# PROG_BATT.net
KiCad netlist of a schematic drawn in EAGLE
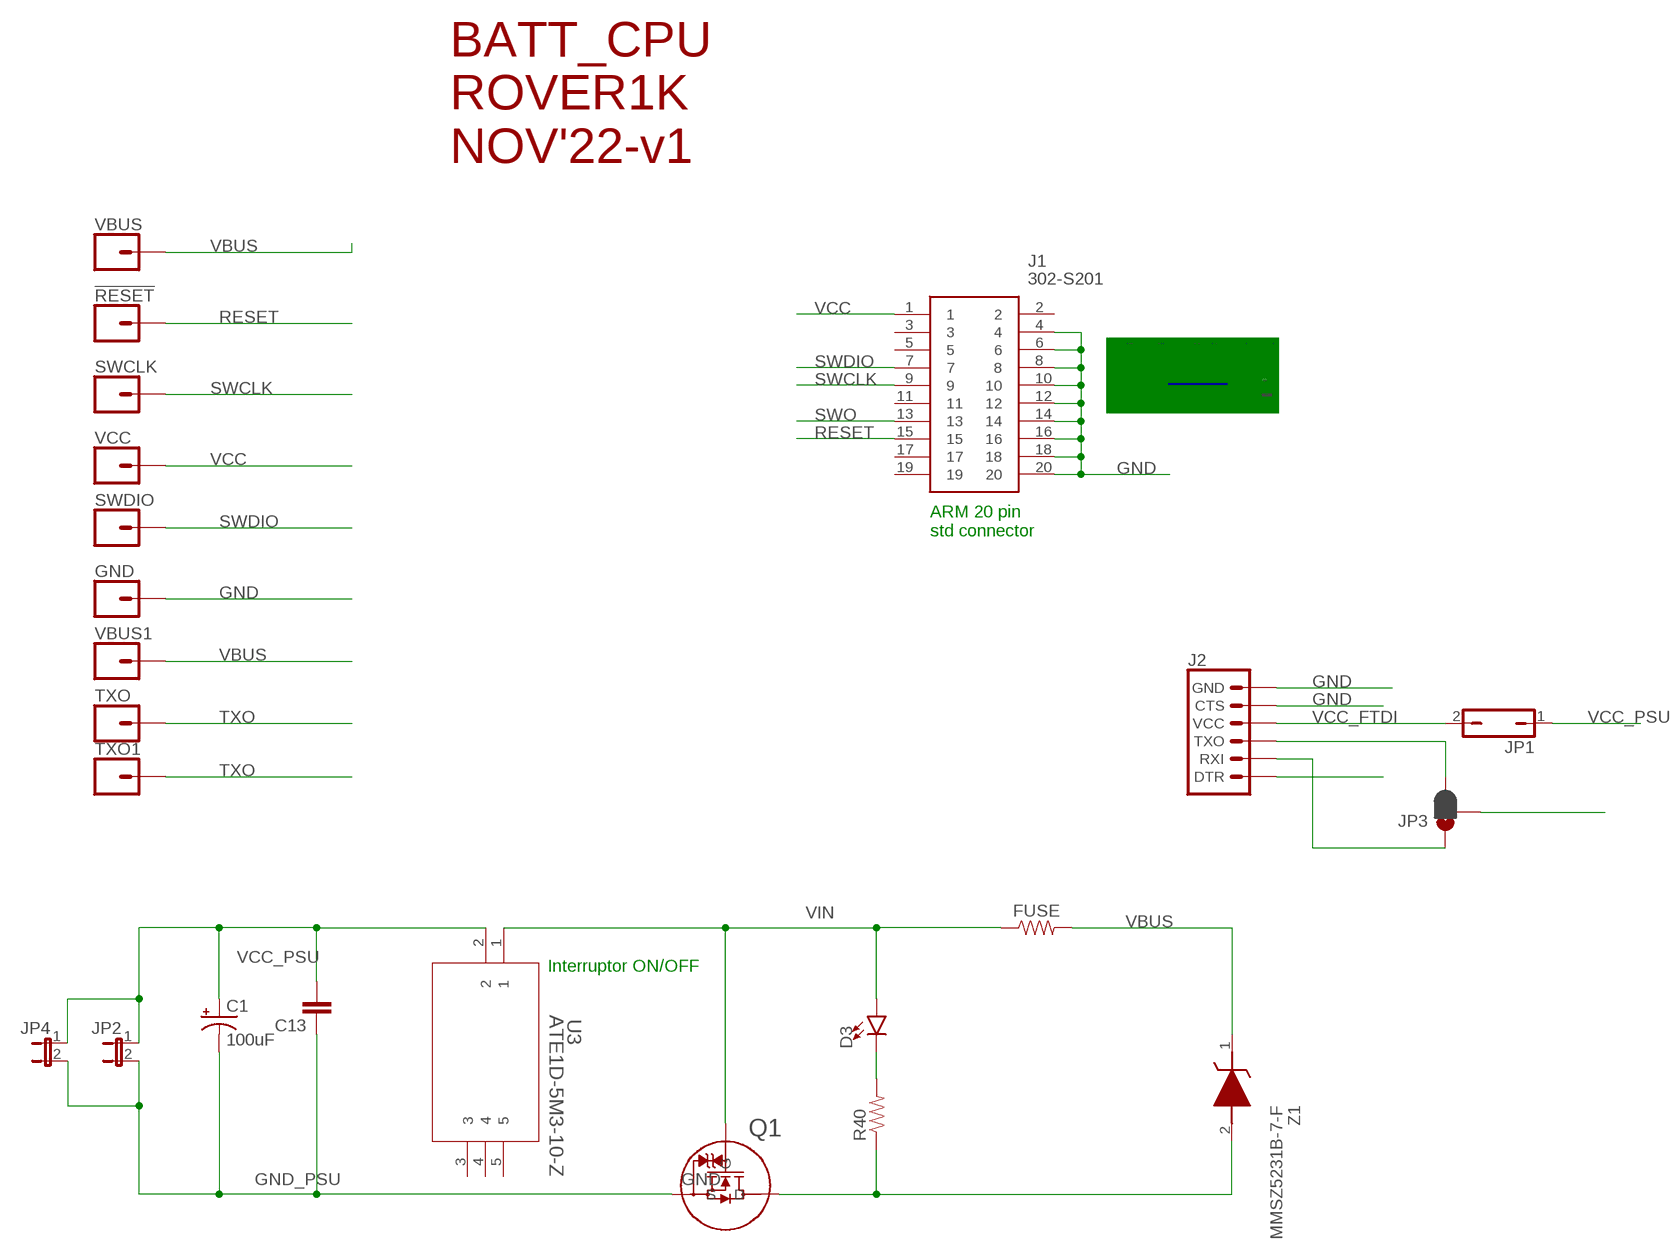
[diagram p0: schematic, sheet 1]

(export (version "E")
  (design (tool "Eeschema 10.0.6"))
  (components
    (comp (ref "!RESET")
      (value "CONN_01POGOPIN_HOLE_LARGE")
      (footprint "eagle-import:1X01_POGOPIN_HOLE_0.061_DIA")
      (libsource (lib "eagle-import") (part "CONN_01POGOPIN_HOLE_LARGE"))
    )
    (comp (ref "C1")
      (value "100uF")
      (footprint "eagle-import:CPOL-RADIAL-2.5MM-6.5MM")
      (libsource (lib "eagle-import") (part "100UF-POLAR-RADIAL-2.5MM-25V-20%"))
    )
    (comp (ref "C13")
      (value "C-EUC0805")
      (footprint "eagle-import:C0805")
      (libsource (lib "eagle-import") (part "C-EUC0805"))
    )
    (comp (ref "D3")
      (value "LED3MM")
      (footprint "eagle-import:LED_3MM")
      (libsource (lib "eagle-import") (part "LED3MM"))
    )
    (comp (ref "FUSE")
      (value "RESISTOR0805")
      (footprint "eagle-import:0805")
      (libsource (lib "eagle-import") (part "RESISTOR0805"))
    )
    (comp (ref "GND")
      (value "CONN_01POGOPIN_HOLE_LARGE")
      (footprint "eagle-import:1X01_POGOPIN_HOLE_0.061_DIA")
      (libsource (lib "eagle-import") (part "CONN_01POGOPIN_HOLE_LARGE"))
    )
    (comp (ref "J1")
      (value "302-S201")
      (footprint "eagle-import:SHDR20W66P254_2X10_3300X905X90")
      (libsource (lib "eagle-import") (part "302-S201"))
    )
    (comp (ref "J2")
      (value "6_PIN_SERIAL_TARGET")
      (footprint "eagle-import:1X06")
      (libsource (lib "eagle-import") (part "6_PIN_SERIAL_TARGET"))
    )
    (comp (ref "JP1")
      (value "JP1Q")
      (footprint "eagle-import:JP1")
      (libsource (lib "eagle-import") (part "JP1Q"))
    )
    (comp (ref "JP2")
      (value "JP1E")
      (footprint "eagle-import:JP1")
      (libsource (lib "eagle-import") (part "JP1E"))
    )
    (comp (ref "JP3")
      (value "JUMPER-SMT_3_1-NC_PASTE_NO-SILK")
      (footprint "eagle-import:SMT-JUMPER_3_1-NC_PASTE_NO-SILK")
      (libsource (lib "eagle-import") (part "JUMPER-SMT_3_1-NC_PASTE_NO-SILK"))
    )
    (comp (ref "JP4")
      (value "JP1E")
      (footprint "eagle-import:JP1")
      (libsource (lib "eagle-import") (part "JP1E"))
    )
    (comp (ref "Q1")
      (value "PJA3416AE_R1_00001")
      (footprint "eagle-import:SOT23_PJA3416_PNJ")
      (fields (field (name "COPYRIGHT") "Copyright (C) 2022 Ultra Librarian. All rights reserved."))
      (libsource (lib "eagle-import") (part "PJA3416AE_R1_00001"))
    )
    (comp (ref "R40")
      (value "10K")
      (footprint "eagle-import:0805")
      (libsource (lib "eagle-import") (part "RESISTOR0805-RES"))
    )
    (comp (ref "SWCLK")
      (value "CONN_01POGOPIN_HOLE_LARGE")
      (footprint "eagle-import:1X01_POGOPIN_HOLE_0.061_DIA")
      (libsource (lib "eagle-import") (part "CONN_01POGOPIN_HOLE_LARGE"))
    )
    (comp (ref "SWDIO")
      (value "CONN_01POGOPIN_HOLE_LARGE")
      (footprint "eagle-import:1X01_POGOPIN_HOLE_0.061_DIA")
      (libsource (lib "eagle-import") (part "CONN_01POGOPIN_HOLE_LARGE"))
    )
    (comp (ref "TXO")
      (value "CONN_01POGOPIN_HOLE_LARGE")
      (footprint "eagle-import:1X01_POGOPIN_HOLE_0.061_DIA")
      (libsource (lib "eagle-import") (part "CONN_01POGOPIN_HOLE_LARGE"))
    )
    (comp (ref "TXO1")
      (value "CONN_01POGOPIN_HOLE_LARGE")
      (footprint "eagle-import:1X01_POGOPIN_HOLE_0.061_DIA")
      (libsource (lib "eagle-import") (part "CONN_01POGOPIN_HOLE_LARGE"))
    )
    (comp (ref "U3")
      (value "ATE1D-5M3-10-Z")
      (footprint "eagle-import:SPDT05_ATE1D_9P5X8_NDC")
      (fields (field (name "COPYRIGHT") "Copyright (C) 2022 Ultra Librarian. All rights reserved."))
      (libsource (lib "eagle-import") (part "ATE1D-5M3-10-Z"))
    )
    (comp (ref "VBUS")
      (value "CONN_01POGOPIN_HOLE_LARGE")
      (footprint "eagle-import:1X01_POGOPIN_HOLE_0.061_DIA")
      (libsource (lib "eagle-import") (part "CONN_01POGOPIN_HOLE_LARGE"))
    )
    (comp (ref "VBUS1")
      (value "CONN_01POGOPIN_HOLE_LARGE")
      (footprint "eagle-import:1X01_POGOPIN_HOLE_0.061_DIA")
      (libsource (lib "eagle-import") (part "CONN_01POGOPIN_HOLE_LARGE"))
    )
    (comp (ref "VCC")
      (value "CONN_01POGOPIN_HOLE_LARGE")
      (footprint "eagle-import:1X01_POGOPIN_HOLE_0.061_DIA")
      (libsource (lib "eagle-import") (part "CONN_01POGOPIN_HOLE_LARGE"))
    )
    (comp (ref "Z1")
      (value "MMSZ5231B-7-F")
      (footprint "eagle-import:SOD3716X145N")
      (fields (field (name "MOUSER_PART_NUMBER") "621-MMSZ5231B-F"))
      (libsource (lib "eagle-import") (part "MMSZ5231B-7-F"))
    )
  )
  (nets
    (net (code "1") (name "/GND") (class "Default")
      (node (ref "GND") (pin "2") (pinfunction "1_2") (pintype "passive"))
      (node (ref "J1") (pin "10") (pinfunction "10_10") (pintype "bidirectional"))
      (node (ref "J1") (pin "12") (pinfunction "12_12") (pintype "bidirectional"))
      (node (ref "J1") (pin "14") (pinfunction "14_14") (pintype "bidirectional"))
      (node (ref "J1") (pin "16") (pinfunction "16_16") (pintype "bidirectional"))
      (node (ref "J1") (pin "18") (pinfunction "18_18") (pintype "bidirectional"))
      (node (ref "J1") (pin "20") (pinfunction "20_20") (pintype "bidirectional"))
      (node (ref "J1") (pin "4") (pinfunction "4_4") (pintype "bidirectional"))
      (node (ref "J1") (pin "6") (pinfunction "6_6") (pintype "bidirectional"))
      (node (ref "J1") (pin "8") (pinfunction "8_8") (pintype "bidirectional"))
      (node (ref "J2") (pin "5") (pinfunction "CTS_5") (pintype "passive"))
      (node (ref "J2") (pin "6") (pinfunction "GND_6") (pintype "passive"))
      (node (ref "Q1") (pin "3") (pinfunction "D_3") (pintype "passive"))
      (node (ref "R40") (pin "1") (pinfunction "1_1") (pintype "passive"))
      (node (ref "Z1") (pin "2") (pinfunction "A_2") (pintype "bidirectional"))
    )
    (net (code "2") (name "/GND_PSU") (class "Default")
      (node (ref "C1") (pin "2") (pinfunction "-_2") (pintype "passive"))
      (node (ref "C13") (pin "1") (pinfunction "1_1") (pintype "passive"))
      (node (ref "JP2") (pin "2") (pinfunction "2_2") (pintype "passive"))
      (node (ref "JP4") (pin "2") (pinfunction "2_2") (pintype "passive"))
      (node (ref "Q1") (pin "2") (pinfunction "S_2") (pintype "passive"))
    )
    (net (code "3") (name "/RESET") (class "Default")
      (node (ref "!RESET") (pin "2") (pinfunction "1_2") (pintype "passive"))
      (node (ref "J1") (pin "15") (pinfunction "15_15") (pintype "bidirectional"))
    )
    (net (code "4") (name "/SWCLK") (class "Default")
      (node (ref "J1") (pin "9") (pinfunction "9_9") (pintype "bidirectional"))
      (node (ref "SWCLK") (pin "2") (pinfunction "1_2") (pintype "passive"))
    )
    (net (code "5") (name "/SWDIO") (class "Default")
      (node (ref "J1") (pin "7") (pinfunction "7_7") (pintype "bidirectional"))
      (node (ref "SWDIO") (pin "2") (pinfunction "1_2") (pintype "passive"))
    )
    (net (code "6") (name "/SWO") (class "Default")
      (node (ref "J1") (pin "13") (pinfunction "13_13") (pintype "bidirectional"))
    )
    (net (code "7") (name "/TXO") (class "Default")
      (node (ref "JP3") (pin "2") (pinfunction "2_2") (pintype "passive"))
      (node (ref "TXO") (pin "2") (pinfunction "1_2") (pintype "passive"))
      (node (ref "TXO1") (pin "2") (pinfunction "1_2") (pintype "passive"))
    )
    (net (code "8") (name "/VBUS") (class "Default")
      (node (ref "FUSE") (pin "2") (pinfunction "2_2") (pintype "passive"))
      (node (ref "VBUS") (pin "2") (pinfunction "1_2") (pintype "passive"))
      (node (ref "VBUS1") (pin "2") (pinfunction "1_2") (pintype "passive"))
      (node (ref "Z1") (pin "1") (pinfunction "K_1") (pintype "bidirectional"))
    )
    (net (code "9") (name "/VCC") (class "Default")
      (node (ref "J1") (pin "1") (pinfunction "1_1") (pintype "bidirectional"))
      (node (ref "VCC") (pin "2") (pinfunction "1_2") (pintype "passive"))
    )
    (net (code "10") (name "/VCC_FTDI") (class "Default")
      (node (ref "J2") (pin "4") (pinfunction "VCC_4") (pintype "passive"))
      (node (ref "JP1") (pin "2") (pinfunction "2_2") (pintype "passive"))
    )
    (net (code "11") (name "/VCC_PSU") (class "Default")
      (node (ref "C1") (pin "1") (pinfunction "+_1") (pintype "passive"))
      (node (ref "C13") (pin "2") (pinfunction "2_2") (pintype "passive"))
      (node (ref "JP1") (pin "1") (pinfunction "1_1") (pintype "passive"))
      (node (ref "JP2") (pin "1") (pinfunction "1_1") (pintype "passive"))
      (node (ref "JP4") (pin "1") (pinfunction "1_1") (pintype "passive"))
      (node (ref "U3") (pin "2") (pinfunction "2_2") (pintype "passive"))
    )
    (net (code "12") (name "/VIN") (class "Default")
      (node (ref "D3") (pin "A") (pinfunction "A_A") (pintype "passive"))
      (node (ref "FUSE") (pin "1") (pinfunction "1_1") (pintype "passive"))
      (node (ref "Q1") (pin "1") (pinfunction "G_1") (pintype "passive"))
      (node (ref "U3") (pin "1") (pinfunction "1_1") (pintype "passive"))
    )
    (net (code "13") (name "Net-(D3-C)") (class "Default")
      (node (ref "D3") (pin "K") (pinfunction "C_K") (pintype "passive"))
      (node (ref "R40") (pin "2") (pinfunction "2_2") (pintype "passive"))
    )
    (net (code "14") (name "Net-(J2-RXI)") (class "Default")
      (node (ref "J2") (pin "2") (pinfunction "RXI_2") (pintype "passive"))
      (node (ref "JP3") (pin "1") (pinfunction "1_1") (pintype "passive"))
    )
    (net (code "15") (name "Net-(J2-TXO)") (class "Default")
      (node (ref "J2") (pin "3") (pinfunction "TXO_3") (pintype "passive"))
      (node (ref "JP3") (pin "3") (pinfunction "3_3") (pintype "passive"))
    )
    (net (code "16") (name "unconnected-(J1-Pad2)") (class "Default")
      (node (ref "J1") (pin "2") (pinfunction "2_2") (pintype "bidirectional"))
    )
    (net (code "17") (name "unconnected-(J1-Pad3)") (class "Default")
      (node (ref "J1") (pin "3") (pinfunction "3_3") (pintype "bidirectional"))
    )
    (net (code "18") (name "unconnected-(J1-Pad5)") (class "Default")
      (node (ref "J1") (pin "5") (pinfunction "5_5") (pintype "bidirectional"))
    )
    (net (code "19") (name "unconnected-(J1-Pad11)") (class "Default")
      (node (ref "J1") (pin "11") (pinfunction "11_11") (pintype "bidirectional"))
    )
    (net (code "20") (name "unconnected-(J1-Pad17)") (class "Default")
      (node (ref "J1") (pin "17") (pinfunction "17_17") (pintype "bidirectional"))
    )
    (net (code "21") (name "unconnected-(J1-Pad19)") (class "Default")
      (node (ref "J1") (pin "19") (pinfunction "19_19") (pintype "bidirectional"))
    )
    (net (code "22") (name "unconnected-(J2-DTR-Pad1)") (class "Default")
      (node (ref "J2") (pin "1") (pinfunction "DTR_1") (pintype "passive"))
    )
    (net (code "23") (name "unconnected-(U3-Pad3)") (class "Default")
      (node (ref "U3") (pin "3") (pinfunction "3_3") (pintype "passive"))
    )
    (net (code "24") (name "unconnected-(U3-Pad4)") (class "Default")
      (node (ref "U3") (pin "4") (pinfunction "4_4") (pintype "passive"))
    )
    (net (code "25") (name "unconnected-(U3-Pad5)") (class "Default")
      (node (ref "U3") (pin "5") (pinfunction "5_5") (pintype "passive"))
    )
  )
)
